# zxclone.net
KiCad netlist of a schematic drawn in EAGLE
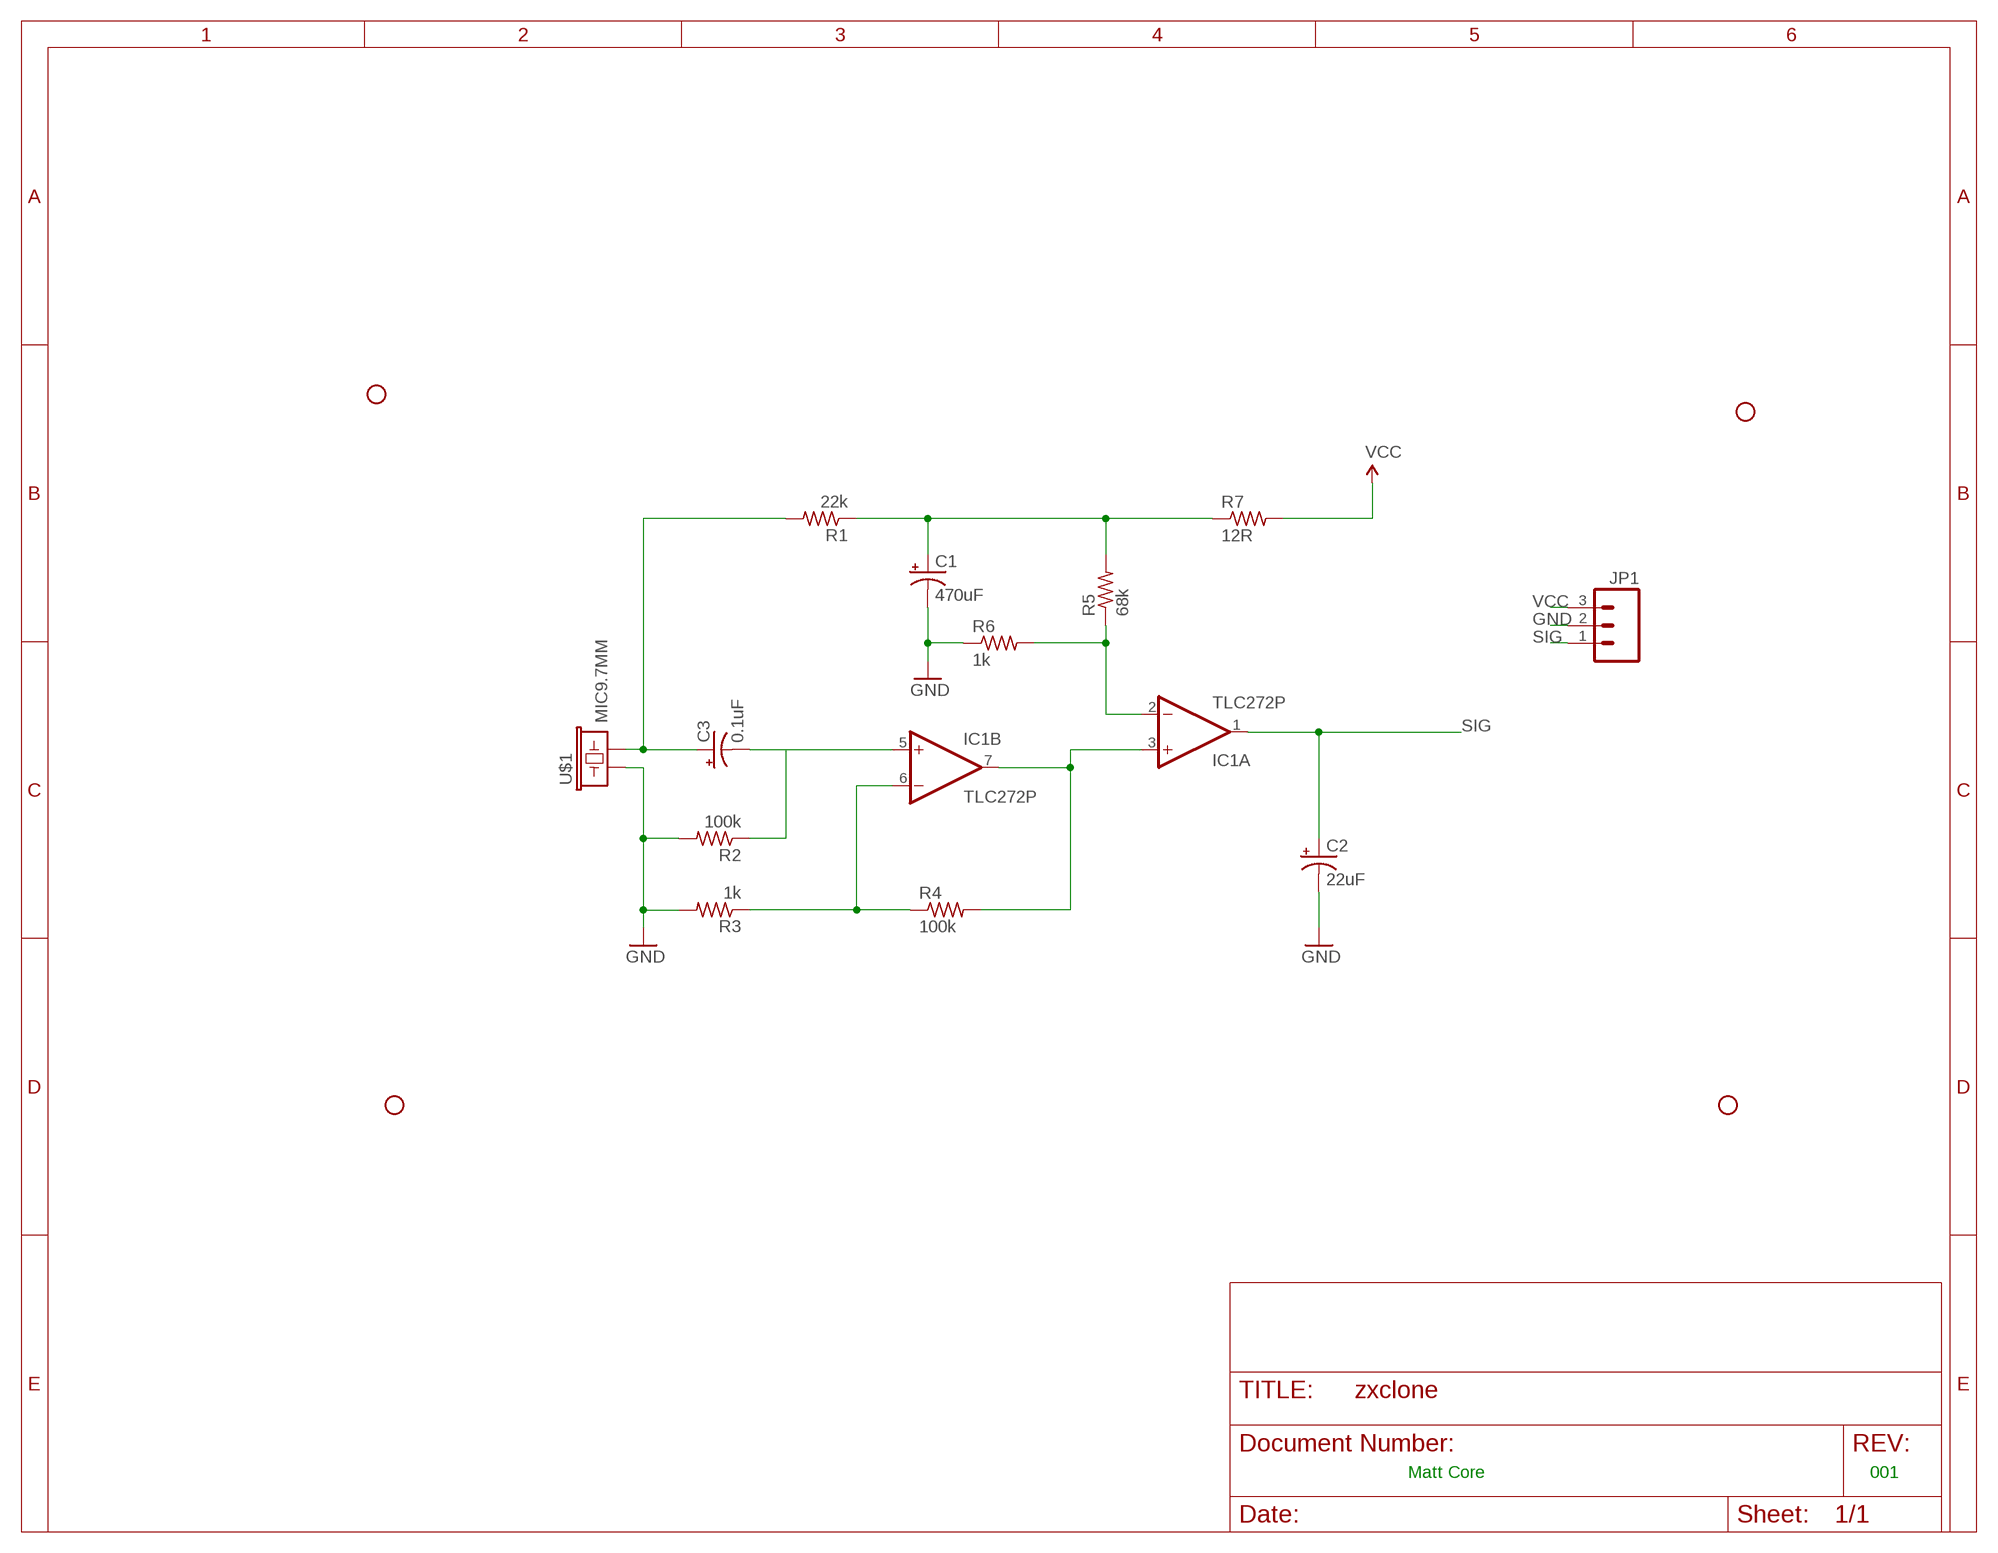
[diagram p0: schematic, sheet 1]

(export (version "E")
  (design (tool "Eeschema 10.0.6"))
  (components
    (comp (ref "C1")
      (value "470uF")
      (footprint "eagle-import:E2,5-7")
      (libsource (lib "eagle-import") (part "CPOL-USE2.5-7"))
    )
    (comp (ref "C2")
      (value "22uF")
      (footprint "eagle-import:E5-4")
      (libsource (lib "eagle-import") (part "CPOL-USE5-4"))
    )
    (comp (ref "C3")
      (value "0.1uF")
      (footprint "eagle-import:E1,8-4")
      (libsource (lib "eagle-import") (part "CPOL-USE1.8-4"))
    )
    (comp (ref "IC1")
      (value "TLC272P")
      (footprint "eagle-import:DIL08")
      (libsource (lib "eagle-import") (part "TLC272P"))
    )
    (comp (ref "JP1")
      (value "M03PTH")
      (footprint "eagle-import:1X03")
      (libsource (lib "eagle-import") (part "M03PTH"))
    )
    (comp (ref "R1")
      (value "22k")
      (footprint "eagle-import:0207_10")
      (libsource (lib "eagle-import") (part "R-US_0207/10"))
    )
    (comp (ref "R2")
      (value "100k")
      (footprint "eagle-import:0207_10")
      (libsource (lib "eagle-import") (part "R-US_0207/10"))
    )
    (comp (ref "R3")
      (value "1k")
      (footprint "eagle-import:0207_10")
      (libsource (lib "eagle-import") (part "R-US_0207/10"))
    )
    (comp (ref "R4")
      (value "100k")
      (footprint "eagle-import:0207_10")
      (libsource (lib "eagle-import") (part "R-US_0207/10"))
    )
    (comp (ref "R5")
      (value "68k")
      (footprint "eagle-import:0207_10")
      (libsource (lib "eagle-import") (part "R-US_0207/10"))
    )
    (comp (ref "R6")
      (value "1k")
      (footprint "eagle-import:0207_10")
      (libsource (lib "eagle-import") (part "R-US_0207/10"))
    )
    (comp (ref "R7")
      (value "12R")
      (footprint "eagle-import:0207_10")
      (libsource (lib "eagle-import") (part "R-US_0207/10"))
    )
    (comp (ref "STANDOFF1")
      (value "STAND-OFF")
      (footprint "eagle-import:STAND-OFF")
      (libsource (lib "eagle-import") (part "STAND-OFF"))
    )
    (comp (ref "STANDOFF2")
      (value "STAND-OFF")
      (footprint "eagle-import:STAND-OFF")
      (libsource (lib "eagle-import") (part "STAND-OFF"))
    )
    (comp (ref "STANDOFF3")
      (value "STAND-OFF")
      (footprint "eagle-import:STAND-OFF")
      (libsource (lib "eagle-import") (part "STAND-OFF"))
    )
    (comp (ref "STANDOFF4")
      (value "STAND-OFF")
      (footprint "eagle-import:STAND-OFF")
      (libsource (lib "eagle-import") (part "STAND-OFF"))
    )
    (comp (ref "U$1")
      (value "MIC9.7MM")
      (footprint "eagle-import:MIC-9.7MM")
      (libsource (lib "eagle-import") (part "MIC9.7MM"))
    )
  )
  (nets
    (net (code "1") (name "/SIG") (class "Default")
      (node (ref "C2") (pin "+") (pinfunction "+_+") (pintype "passive"))
      (node (ref "IC1") (pin "1") (pinfunction "OUT_1") (pintype "output"))
      (node (ref "JP1") (pin "1") (pinfunction "1_1") (pintype "passive"))
    )
    (net (code "2") (name "GND") (class "Default")
      (node (ref "C1") (pin "-") (pinfunction "-_-") (pintype "passive"))
      (node (ref "C2") (pin "-") (pinfunction "-_-") (pintype "passive"))
      (node (ref "JP1") (pin "2") (pinfunction "2_2") (pintype "passive"))
      (node (ref "R2") (pin "2") (pinfunction "2_2") (pintype "passive"))
      (node (ref "R3") (pin "2") (pinfunction "2_2") (pintype "passive"))
      (node (ref "R6") (pin "1") (pinfunction "1_1") (pintype "passive"))
      (node (ref "U$1") (pin "1") (pinfunction "1_1") (pintype "passive"))
    )
    (net (code "3") (name "Net-(C1-Pad+)") (class "Default")
      (node (ref "C1") (pin "+") (pinfunction "+_+") (pintype "passive"))
      (node (ref "R1") (pin "1") (pinfunction "1_1") (pintype "passive"))
      (node (ref "R5") (pin "2") (pinfunction "2_2") (pintype "passive"))
      (node (ref "R7") (pin "1") (pinfunction "1_1") (pintype "passive"))
    )
    (net (code "4") (name "Net-(C3-Pad+)") (class "Default")
      (node (ref "C3") (pin "+") (pinfunction "+_+") (pintype "passive"))
      (node (ref "R1") (pin "2") (pinfunction "2_2") (pintype "passive"))
      (node (ref "U$1") (pin "2") (pinfunction "2_2") (pintype "passive"))
    )
    (net (code "5") (name "Net-(IC1A-+IN)") (class "Default")
      (node (ref "IC1") (pin "3") (pinfunction "+IN_3") (pintype "input"))
      (node (ref "IC1") (pin "7") (pinfunction "OUT_7") (pintype "output"))
      (node (ref "R4") (pin "2") (pinfunction "2_2") (pintype "passive"))
    )
    (net (code "6") (name "Net-(IC1A--IN)") (class "Default")
      (node (ref "IC1") (pin "2") (pinfunction "-IN_2") (pintype "input"))
      (node (ref "R5") (pin "1") (pinfunction "1_1") (pintype "passive"))
      (node (ref "R6") (pin "2") (pinfunction "2_2") (pintype "passive"))
    )
    (net (code "7") (name "Net-(IC1B-+IN)") (class "Default")
      (node (ref "C3") (pin "-") (pinfunction "-_-") (pintype "passive"))
      (node (ref "IC1") (pin "5") (pinfunction "+IN_5") (pintype "input"))
      (node (ref "R2") (pin "1") (pinfunction "1_1") (pintype "passive"))
    )
    (net (code "8") (name "Net-(IC1B--IN)") (class "Default")
      (node (ref "IC1") (pin "6") (pinfunction "-IN_6") (pintype "input"))
      (node (ref "R3") (pin "1") (pinfunction "1_1") (pintype "passive"))
      (node (ref "R4") (pin "1") (pinfunction "1_1") (pintype "passive"))
    )
    (net (code "9") (name "VCC") (class "Default")
      (node (ref "JP1") (pin "3") (pinfunction "3_3") (pintype "passive"))
      (node (ref "R7") (pin "2") (pinfunction "2_2") (pintype "passive"))
    )
  )
)
